# Connectors.net
KiCad netlist of a schematic drawn in Altium Designer
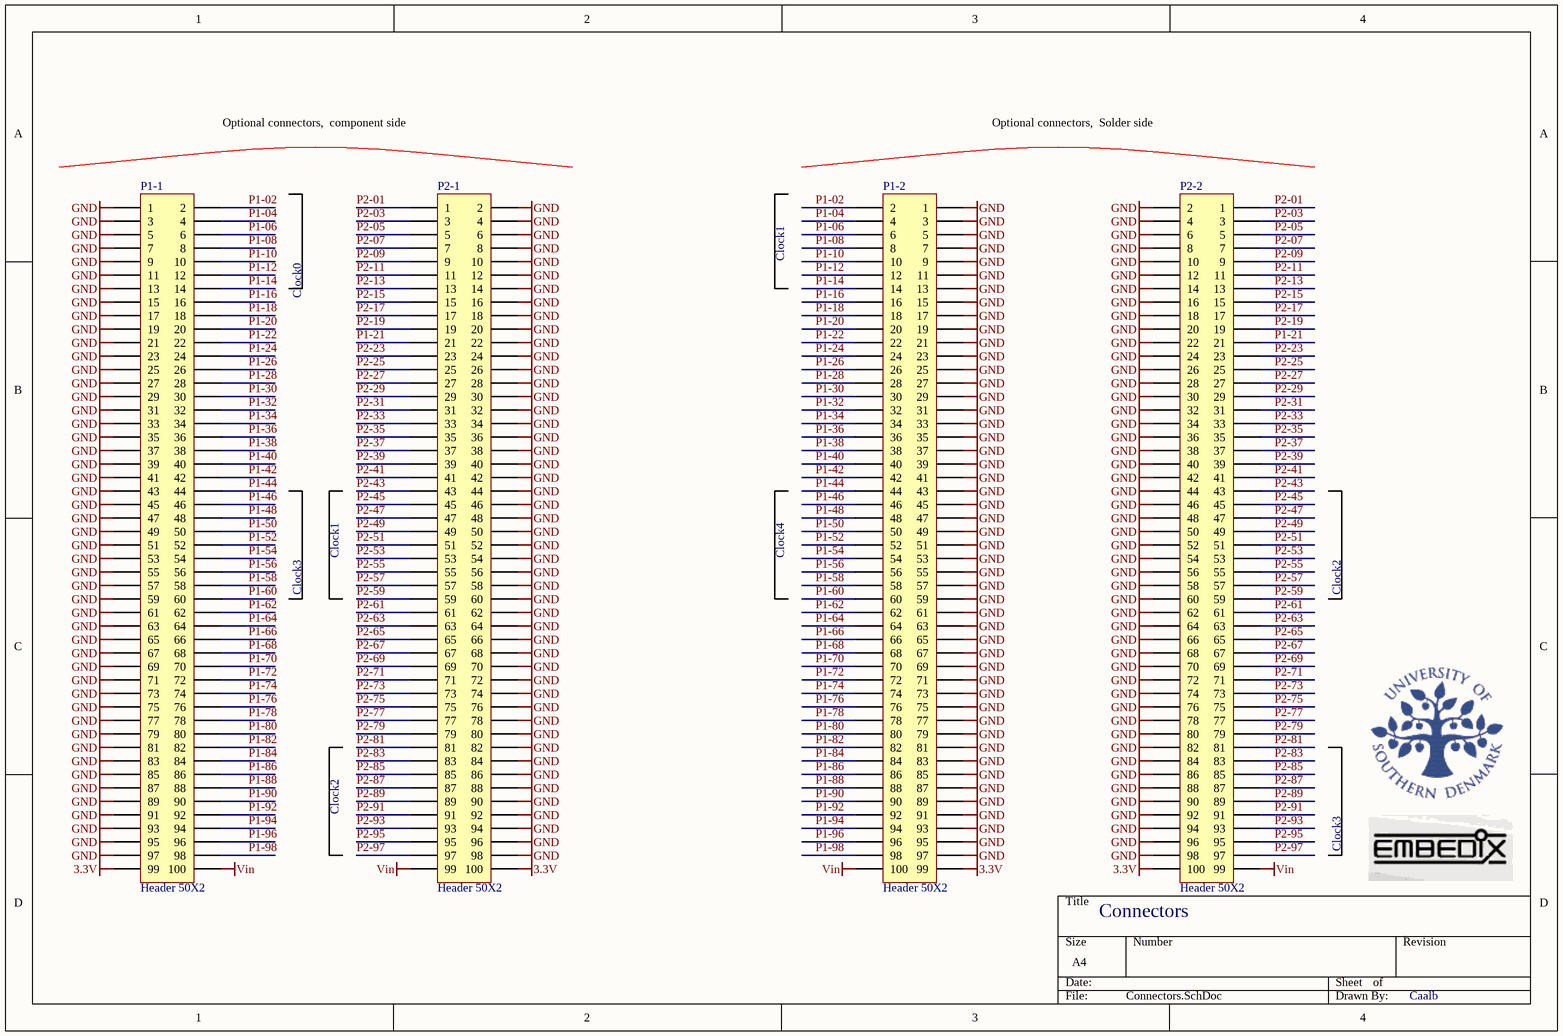
[diagram p0: Connectors.SchDoc]

(export (version "E")
  (design (tool "Eeschema 10.0.6"))
  (components
    (comp (ref "P1-1")
      (value "Header 50X2")
      (footprint "FX8C-100S-SV(91)")
      (description "FX8C-100S-SV(91)")
      (fields (field (name "PUBLISHER") "Altium Limited"))
      (libsource (lib "") (part "Header 50X2_1"))
    )
    (comp (ref "P1-2")
      (value "Header 50X2")
      (footprint "FX8C-100P-SV6(91)")
      (description "FX8C-100P-SV6(91)")
      (fields (field (name "PUBLISHER") "Altium Limited"))
      (libsource (lib "DivLib") (part "Header 50X2"))
    )
    (comp (ref "P2-1")
      (value "Header 50X2")
      (footprint "FX8C-100S-SV(91)")
      (description "FX8C-100S-SV(91)")
      (fields (field (name "PUBLISHER") "Altium Limited"))
      (libsource (lib "") (part "Header 50X2_1"))
    )
    (comp (ref "P2-2")
      (value "Header 50X2")
      (footprint "FX8C-100P-SV6(91)")
      (description "FX8C-100P-SV6(91)")
      (fields (field (name "PUBLISHER") "Altium Limited"))
      (libsource (lib "DivLib") (part "Header 50X2"))
    )
  )
  (nets
    (net (code "1") (name "/P1-02") (class "Default")
      (node (ref "P1-1") (pin "2") (pinfunction "2_2") (pintype "passive"))
      (node (ref "P1-2") (pin "2") (pinfunction "2_2") (pintype "passive"))
    )
    (net (code "2") (name "/P1-04") (class "Default")
      (node (ref "P1-1") (pin "4") (pinfunction "4_4") (pintype "passive"))
      (node (ref "P1-2") (pin "4") (pinfunction "4_4") (pintype "passive"))
    )
    (net (code "3") (name "/P1-06") (class "Default")
      (node (ref "P1-1") (pin "6") (pinfunction "6_6") (pintype "passive"))
      (node (ref "P1-2") (pin "6") (pinfunction "6_6") (pintype "passive"))
    )
    (net (code "4") (name "/P1-08") (class "Default")
      (node (ref "P1-1") (pin "8") (pinfunction "8_8") (pintype "passive"))
      (node (ref "P1-2") (pin "8") (pinfunction "8_8") (pintype "passive"))
    )
    (net (code "5") (name "/P1-10") (class "Default")
      (node (ref "P1-1") (pin "10") (pinfunction "10_10") (pintype "passive"))
      (node (ref "P1-2") (pin "10") (pinfunction "10_10") (pintype "passive"))
    )
    (net (code "6") (name "/P1-12") (class "Default")
      (node (ref "P1-1") (pin "12") (pinfunction "12_12") (pintype "passive"))
      (node (ref "P1-2") (pin "12") (pinfunction "12_12") (pintype "passive"))
    )
    (net (code "7") (name "/P1-14") (class "Default")
      (node (ref "P1-1") (pin "14") (pinfunction "14_14") (pintype "passive"))
      (node (ref "P1-2") (pin "14") (pinfunction "14_14") (pintype "passive"))
    )
    (net (code "8") (name "/P1-16") (class "Default")
      (node (ref "P1-1") (pin "16") (pinfunction "16_16") (pintype "passive"))
      (node (ref "P1-2") (pin "16") (pinfunction "16_16") (pintype "passive"))
    )
    (net (code "9") (name "/P1-18") (class "Default")
      (node (ref "P1-1") (pin "18") (pinfunction "18_18") (pintype "passive"))
      (node (ref "P1-2") (pin "18") (pinfunction "18_18") (pintype "passive"))
    )
    (net (code "10") (name "/P1-20") (class "Default")
      (node (ref "P1-1") (pin "20") (pinfunction "20_20") (pintype "passive"))
      (node (ref "P1-2") (pin "20") (pinfunction "20_20") (pintype "passive"))
    )
    (net (code "11") (name "/P1-21") (class "Default")
      (node (ref "P2-1") (pin "21") (pinfunction "21_21") (pintype "passive"))
      (node (ref "P2-2") (pin "21") (pinfunction "21_21") (pintype "passive"))
    )
    (net (code "12") (name "/P1-22") (class "Default")
      (node (ref "P1-1") (pin "22") (pinfunction "22_22") (pintype "passive"))
      (node (ref "P1-2") (pin "22") (pinfunction "22_22") (pintype "passive"))
    )
    (net (code "13") (name "/P1-24") (class "Default")
      (node (ref "P1-1") (pin "24") (pinfunction "24_24") (pintype "passive"))
      (node (ref "P1-2") (pin "24") (pinfunction "24_24") (pintype "passive"))
    )
    (net (code "14") (name "/P1-26") (class "Default")
      (node (ref "P1-1") (pin "26") (pinfunction "26_26") (pintype "passive"))
      (node (ref "P1-2") (pin "26") (pinfunction "26_26") (pintype "passive"))
    )
    (net (code "15") (name "/P1-28") (class "Default")
      (node (ref "P1-1") (pin "28") (pinfunction "28_28") (pintype "passive"))
      (node (ref "P1-2") (pin "28") (pinfunction "28_28") (pintype "passive"))
    )
    (net (code "16") (name "/P1-30") (class "Default")
      (node (ref "P1-1") (pin "30") (pinfunction "30_30") (pintype "passive"))
      (node (ref "P1-2") (pin "30") (pinfunction "30_30") (pintype "passive"))
    )
    (net (code "17") (name "/P1-32") (class "Default")
      (node (ref "P1-1") (pin "32") (pinfunction "32_32") (pintype "passive"))
      (node (ref "P1-2") (pin "32") (pinfunction "32_32") (pintype "passive"))
    )
    (net (code "18") (name "/P1-34") (class "Default")
      (node (ref "P1-1") (pin "34") (pinfunction "34_34") (pintype "passive"))
      (node (ref "P1-2") (pin "34") (pinfunction "34_34") (pintype "passive"))
    )
    (net (code "19") (name "/P1-36") (class "Default")
      (node (ref "P1-1") (pin "36") (pinfunction "36_36") (pintype "passive"))
      (node (ref "P1-2") (pin "36") (pinfunction "36_36") (pintype "passive"))
    )
    (net (code "20") (name "/P1-38") (class "Default")
      (node (ref "P1-1") (pin "38") (pinfunction "38_38") (pintype "passive"))
      (node (ref "P1-2") (pin "38") (pinfunction "38_38") (pintype "passive"))
    )
    (net (code "21") (name "/P1-40") (class "Default")
      (node (ref "P1-1") (pin "40") (pinfunction "40_40") (pintype "passive"))
      (node (ref "P1-2") (pin "40") (pinfunction "40_40") (pintype "passive"))
    )
    (net (code "22") (name "/P1-42") (class "Default")
      (node (ref "P1-1") (pin "42") (pinfunction "42_42") (pintype "passive"))
      (node (ref "P1-2") (pin "42") (pinfunction "42_42") (pintype "passive"))
    )
    (net (code "23") (name "/P1-44") (class "Default")
      (node (ref "P1-1") (pin "44") (pinfunction "44_44") (pintype "passive"))
      (node (ref "P1-2") (pin "44") (pinfunction "44_44") (pintype "passive"))
    )
    (net (code "24") (name "/P1-46") (class "Default")
      (node (ref "P1-1") (pin "46") (pinfunction "46_46") (pintype "passive"))
      (node (ref "P1-2") (pin "46") (pinfunction "46_46") (pintype "passive"))
    )
    (net (code "25") (name "/P1-48") (class "Default")
      (node (ref "P1-1") (pin "48") (pinfunction "48_48") (pintype "passive"))
      (node (ref "P1-2") (pin "48") (pinfunction "48_48") (pintype "passive"))
    )
    (net (code "26") (name "/P1-50") (class "Default")
      (node (ref "P1-1") (pin "50") (pinfunction "50_50") (pintype "passive"))
      (node (ref "P1-2") (pin "50") (pinfunction "50_50") (pintype "passive"))
    )
    (net (code "27") (name "/P1-52") (class "Default")
      (node (ref "P1-1") (pin "52") (pinfunction "52_52") (pintype "passive"))
      (node (ref "P1-2") (pin "52") (pinfunction "52_52") (pintype "passive"))
    )
    (net (code "28") (name "/P1-54") (class "Default")
      (node (ref "P1-1") (pin "54") (pinfunction "54_54") (pintype "passive"))
      (node (ref "P1-2") (pin "54") (pinfunction "54_54") (pintype "passive"))
    )
    (net (code "29") (name "/P1-56") (class "Default")
      (node (ref "P1-1") (pin "56") (pinfunction "56_56") (pintype "passive"))
      (node (ref "P1-2") (pin "56") (pinfunction "56_56") (pintype "passive"))
    )
    (net (code "30") (name "/P1-58") (class "Default")
      (node (ref "P1-1") (pin "58") (pinfunction "58_58") (pintype "passive"))
      (node (ref "P1-2") (pin "58") (pinfunction "58_58") (pintype "passive"))
    )
    (net (code "31") (name "/P1-60") (class "Default")
      (node (ref "P1-1") (pin "60") (pinfunction "60_60") (pintype "passive"))
      (node (ref "P1-2") (pin "60") (pinfunction "60_60") (pintype "passive"))
    )
    (net (code "32") (name "/P1-62") (class "Default")
      (node (ref "P1-1") (pin "62") (pinfunction "62_62") (pintype "passive"))
      (node (ref "P1-2") (pin "62") (pinfunction "62_62") (pintype "passive"))
    )
    (net (code "33") (name "/P1-64") (class "Default")
      (node (ref "P1-1") (pin "64") (pinfunction "64_64") (pintype "passive"))
      (node (ref "P1-2") (pin "64") (pinfunction "64_64") (pintype "passive"))
    )
    (net (code "34") (name "/P1-66") (class "Default")
      (node (ref "P1-1") (pin "66") (pinfunction "66_66") (pintype "passive"))
      (node (ref "P1-2") (pin "66") (pinfunction "66_66") (pintype "passive"))
    )
    (net (code "35") (name "/P1-68") (class "Default")
      (node (ref "P1-1") (pin "68") (pinfunction "68_68") (pintype "passive"))
      (node (ref "P1-2") (pin "68") (pinfunction "68_68") (pintype "passive"))
    )
    (net (code "36") (name "/P1-70") (class "Default")
      (node (ref "P1-1") (pin "70") (pinfunction "70_70") (pintype "passive"))
      (node (ref "P1-2") (pin "70") (pinfunction "70_70") (pintype "passive"))
    )
    (net (code "37") (name "/P1-72") (class "Default")
      (node (ref "P1-1") (pin "72") (pinfunction "72_72") (pintype "passive"))
      (node (ref "P1-2") (pin "72") (pinfunction "72_72") (pintype "passive"))
    )
    (net (code "38") (name "/P1-74") (class "Default")
      (node (ref "P1-1") (pin "74") (pinfunction "74_74") (pintype "passive"))
      (node (ref "P1-2") (pin "74") (pinfunction "74_74") (pintype "passive"))
    )
    (net (code "39") (name "/P1-76") (class "Default")
      (node (ref "P1-1") (pin "76") (pinfunction "76_76") (pintype "passive"))
      (node (ref "P1-2") (pin "76") (pinfunction "76_76") (pintype "passive"))
    )
    (net (code "40") (name "/P1-78") (class "Default")
      (node (ref "P1-1") (pin "78") (pinfunction "78_78") (pintype "passive"))
      (node (ref "P1-2") (pin "78") (pinfunction "78_78") (pintype "passive"))
    )
    (net (code "41") (name "/P1-80") (class "Default")
      (node (ref "P1-1") (pin "80") (pinfunction "80_80") (pintype "passive"))
      (node (ref "P1-2") (pin "80") (pinfunction "80_80") (pintype "passive"))
    )
    (net (code "42") (name "/P1-82") (class "Default")
      (node (ref "P1-1") (pin "82") (pinfunction "82_82") (pintype "passive"))
      (node (ref "P1-2") (pin "82") (pinfunction "82_82") (pintype "passive"))
    )
    (net (code "43") (name "/P1-84") (class "Default")
      (node (ref "P1-1") (pin "84") (pinfunction "84_84") (pintype "passive"))
      (node (ref "P1-2") (pin "84") (pinfunction "84_84") (pintype "passive"))
    )
    (net (code "44") (name "/P1-86") (class "Default")
      (node (ref "P1-1") (pin "86") (pinfunction "86_86") (pintype "passive"))
      (node (ref "P1-2") (pin "86") (pinfunction "86_86") (pintype "passive"))
    )
    (net (code "45") (name "/P1-88") (class "Default")
      (node (ref "P1-1") (pin "88") (pinfunction "88_88") (pintype "passive"))
      (node (ref "P1-2") (pin "88") (pinfunction "88_88") (pintype "passive"))
    )
    (net (code "46") (name "/P1-90") (class "Default")
      (node (ref "P1-1") (pin "90") (pinfunction "90_90") (pintype "passive"))
      (node (ref "P1-2") (pin "90") (pinfunction "90_90") (pintype "passive"))
    )
    (net (code "47") (name "/P1-92") (class "Default")
      (node (ref "P1-1") (pin "92") (pinfunction "92_92") (pintype "passive"))
      (node (ref "P1-2") (pin "92") (pinfunction "92_92") (pintype "passive"))
    )
    (net (code "48") (name "/P1-94") (class "Default")
      (node (ref "P1-1") (pin "94") (pinfunction "94_94") (pintype "passive"))
      (node (ref "P1-2") (pin "94") (pinfunction "94_94") (pintype "passive"))
    )
    (net (code "49") (name "/P1-96") (class "Default")
      (node (ref "P1-1") (pin "96") (pinfunction "96_96") (pintype "passive"))
      (node (ref "P1-2") (pin "96") (pinfunction "96_96") (pintype "passive"))
    )
    (net (code "50") (name "/P1-98") (class "Default")
      (node (ref "P1-1") (pin "98") (pinfunction "98_98") (pintype "passive"))
      (node (ref "P1-2") (pin "98") (pinfunction "98_98") (pintype "passive"))
    )
    (net (code "51") (name "/P2-01") (class "Default")
      (node (ref "P2-1") (pin "1") (pinfunction "1_1") (pintype "passive"))
      (node (ref "P2-2") (pin "1") (pinfunction "1_1") (pintype "passive"))
    )
    (net (code "52") (name "/P2-03") (class "Default")
      (node (ref "P2-1") (pin "3") (pinfunction "3_3") (pintype "passive"))
      (node (ref "P2-2") (pin "3") (pinfunction "3_3") (pintype "passive"))
    )
    (net (code "53") (name "/P2-05") (class "Default")
      (node (ref "P2-1") (pin "5") (pinfunction "5_5") (pintype "passive"))
      (node (ref "P2-2") (pin "5") (pinfunction "5_5") (pintype "passive"))
    )
    (net (code "54") (name "/P2-07") (class "Default")
      (node (ref "P2-1") (pin "7") (pinfunction "7_7") (pintype "passive"))
      (node (ref "P2-2") (pin "7") (pinfunction "7_7") (pintype "passive"))
    )
    (net (code "55") (name "/P2-09") (class "Default")
      (node (ref "P2-1") (pin "9") (pinfunction "9_9") (pintype "passive"))
      (node (ref "P2-2") (pin "9") (pinfunction "9_9") (pintype "passive"))
    )
    (net (code "56") (name "/P2-11") (class "Default")
      (node (ref "P2-1") (pin "11") (pinfunction "11_11") (pintype "passive"))
      (node (ref "P2-2") (pin "11") (pinfunction "11_11") (pintype "passive"))
    )
    (net (code "57") (name "/P2-13") (class "Default")
      (node (ref "P2-1") (pin "13") (pinfunction "13_13") (pintype "passive"))
      (node (ref "P2-2") (pin "13") (pinfunction "13_13") (pintype "passive"))
    )
    (net (code "58") (name "/P2-15") (class "Default")
      (node (ref "P2-1") (pin "15") (pinfunction "15_15") (pintype "passive"))
      (node (ref "P2-2") (pin "15") (pinfunction "15_15") (pintype "passive"))
    )
    (net (code "59") (name "/P2-17") (class "Default")
      (node (ref "P2-1") (pin "17") (pinfunction "17_17") (pintype "passive"))
      (node (ref "P2-2") (pin "17") (pinfunction "17_17") (pintype "passive"))
    )
    (net (code "60") (name "/P2-19") (class "Default")
      (node (ref "P2-1") (pin "19") (pinfunction "19_19") (pintype "passive"))
      (node (ref "P2-2") (pin "19") (pinfunction "19_19") (pintype "passive"))
    )
    (net (code "61") (name "/P2-23") (class "Default")
      (node (ref "P2-1") (pin "23") (pinfunction "23_23") (pintype "passive"))
      (node (ref "P2-2") (pin "23") (pinfunction "23_23") (pintype "passive"))
    )
    (net (code "62") (name "/P2-25") (class "Default")
      (node (ref "P2-1") (pin "25") (pinfunction "25_25") (pintype "passive"))
      (node (ref "P2-2") (pin "25") (pinfunction "25_25") (pintype "passive"))
    )
    (net (code "63") (name "/P2-27") (class "Default")
      (node (ref "P2-1") (pin "27") (pinfunction "27_27") (pintype "passive"))
      (node (ref "P2-2") (pin "27") (pinfunction "27_27") (pintype "passive"))
    )
    (net (code "64") (name "/P2-29") (class "Default")
      (node (ref "P2-1") (pin "29") (pinfunction "29_29") (pintype "passive"))
      (node (ref "P2-2") (pin "29") (pinfunction "29_29") (pintype "passive"))
    )
    (net (code "65") (name "/P2-31") (class "Default")
      (node (ref "P2-1") (pin "31") (pinfunction "31_31") (pintype "passive"))
      (node (ref "P2-2") (pin "31") (pinfunction "31_31") (pintype "passive"))
    )
    (net (code "66") (name "/P2-33") (class "Default")
      (node (ref "P2-1") (pin "33") (pinfunction "33_33") (pintype "passive"))
      (node (ref "P2-2") (pin "33") (pinfunction "33_33") (pintype "passive"))
    )
    (net (code "67") (name "/P2-35") (class "Default")
      (node (ref "P2-1") (pin "35") (pinfunction "35_35") (pintype "passive"))
      (node (ref "P2-2") (pin "35") (pinfunction "35_35") (pintype "passive"))
    )
    (net (code "68") (name "/P2-37") (class "Default")
      (node (ref "P2-1") (pin "37") (pinfunction "37_37") (pintype "passive"))
      (node (ref "P2-2") (pin "37") (pinfunction "37_37") (pintype "passive"))
    )
    (net (code "69") (name "/P2-39") (class "Default")
      (node (ref "P2-1") (pin "39") (pinfunction "39_39") (pintype "passive"))
      (node (ref "P2-2") (pin "39") (pinfunction "39_39") (pintype "passive"))
    )
    (net (code "70") (name "/P2-41") (class "Default")
      (node (ref "P2-1") (pin "41") (pinfunction "41_41") (pintype "passive"))
      (node (ref "P2-2") (pin "41") (pinfunction "41_41") (pintype "passive"))
    )
    (net (code "71") (name "/P2-43") (class "Default")
      (node (ref "P2-1") (pin "43") (pinfunction "43_43") (pintype "passive"))
      (node (ref "P2-2") (pin "43") (pinfunction "43_43") (pintype "passive"))
    )
    (net (code "72") (name "/P2-45") (class "Default")
      (node (ref "P2-1") (pin "45") (pinfunction "45_45") (pintype "passive"))
      (node (ref "P2-2") (pin "45") (pinfunction "45_45") (pintype "passive"))
    )
    (net (code "73") (name "/P2-47") (class "Default")
      (node (ref "P2-1") (pin "47") (pinfunction "47_47") (pintype "passive"))
      (node (ref "P2-2") (pin "47") (pinfunction "47_47") (pintype "passive"))
    )
    (net (code "74") (name "/P2-49") (class "Default")
      (node (ref "P2-1") (pin "49") (pinfunction "49_49") (pintype "passive"))
      (node (ref "P2-2") (pin "49") (pinfunction "49_49") (pintype "passive"))
    )
    (net (code "75") (name "/P2-51") (class "Default")
      (node (ref "P2-1") (pin "51") (pinfunction "51_51") (pintype "passive"))
      (node (ref "P2-2") (pin "51") (pinfunction "51_51") (pintype "passive"))
    )
    (net (code "76") (name "/P2-53") (class "Default")
      (node (ref "P2-1") (pin "53") (pinfunction "53_53") (pintype "passive"))
      (node (ref "P2-2") (pin "53") (pinfunction "53_53") (pintype "passive"))
    )
    (net (code "77") (name "/P2-55") (class "Default")
      (node (ref "P2-1") (pin "55") (pinfunction "55_55") (pintype "passive"))
      (node (ref "P2-2") (pin "55") (pinfunction "55_55") (pintype "passive"))
    )
    (net (code "78") (name "/P2-57") (class "Default")
      (node (ref "P2-1") (pin "57") (pinfunction "57_57") (pintype "passive"))
      (node (ref "P2-2") (pin "57") (pinfunction "57_57") (pintype "passive"))
    )
    (net (code "79") (name "/P2-59") (class "Default")
      (node (ref "P2-1") (pin "59") (pinfunction "59_59") (pintype "passive"))
      (node (ref "P2-2") (pin "59") (pinfunction "59_59") (pintype "passive"))
    )
    (net (code "80") (name "/P2-61") (class "Default")
      (node (ref "P2-1") (pin "61") (pinfunction "61_61") (pintype "passive"))
      (node (ref "P2-2") (pin "61") (pinfunction "61_61") (pintype "passive"))
    )
    (net (code "81") (name "/P2-63") (class "Default")
      (node (ref "P2-1") (pin "63") (pinfunction "63_63") (pintype "passive"))
      (node (ref "P2-2") (pin "63") (pinfunction "63_63") (pintype "passive"))
    )
    (net (code "82") (name "/P2-65") (class "Default")
      (node (ref "P2-1") (pin "65") (pinfunction "65_65") (pintype "passive"))
      (node (ref "P2-2") (pin "65") (pinfunction "65_65") (pintype "passive"))
    )
    (net (code "83") (name "/P2-67") (class "Default")
      (node (ref "P2-1") (pin "67") (pinfunction "67_67") (pintype "passive"))
      (node (ref "P2-2") (pin "67") (pinfunction "67_67") (pintype "passive"))
    )
    (net (code "84") (name "/P2-69") (class "Default")
      (node (ref "P2-1") (pin "69") (pinfunction "69_69") (pintype "passive"))
      (node (ref "P2-2") (pin "69") (pinfunction "69_69") (pintype "passive"))
    )
    (net (code "85") (name "/P2-71") (class "Default")
      (node (ref "P2-1") (pin "71") (pinfunction "71_71") (pintype "passive"))
      (node (ref "P2-2") (pin "71") (pinfunction "71_71") (pintype "passive"))
    )
    (net (code "86") (name "/P2-73") (class "Default")
      (node (ref "P2-1") (pin "73") (pinfunction "73_73") (pintype "passive"))
      (node (ref "P2-2") (pin "73") (pinfunction "73_73") (pintype "passive"))
    )
    (net (code "87") (name "/P2-75") (class "Default")
      (node (ref "P2-1") (pin "75") (pinfunction "75_75") (pintype "passive"))
      (node (ref "P2-2") (pin "75") (pinfunction "75_75") (pintype "passive"))
    )
    (net (code "88") (name "/P2-77") (class "Default")
      (node (ref "P2-1") (pin "77") (pinfunction "77_77") (pintype "passive"))
      (node (ref "P2-2") (pin "77") (pinfunction "77_77") (pintype "passive"))
    )
    (net (code "89") (name "/P2-79") (class "Default")
      (node (ref "P2-1") (pin "79") (pinfunction "79_79") (pintype "passive"))
      (node (ref "P2-2") (pin "79") (pinfunction "79_79") (pintype "passive"))
    )
    (net (code "90") (name "/P2-81") (class "Default")
      (node (ref "P2-1") (pin "81") (pinfunction "81_81") (pintype "passive"))
      (node (ref "P2-2") (pin "81") (pinfunction "81_81") (pintype "passive"))
    )
    (net (code "91") (name "/P2-83") (class "Default")
      (node (ref "P2-1") (pin "83") (pinfunction "83_83") (pintype "passive"))
      (node (ref "P2-2") (pin "83") (pinfunction "83_83") (pintype "passive"))
    )
    (net (code "92") (name "/P2-85") (class "Default")
      (node (ref "P2-1") (pin "85") (pinfunction "85_85") (pintype "passive"))
      (node (ref "P2-2") (pin "85") (pinfunction "85_85") (pintype "passive"))
    )
    (net (code "93") (name "/P2-87") (class "Default")
      (node (ref "P2-1") (pin "87") (pinfunction "87_87") (pintype "passive"))
      (node (ref "P2-2") (pin "87") (pinfunction "87_87") (pintype "passive"))
    )
    (net (code "94") (name "/P2-89") (class "Default")
      (node (ref "P2-1") (pin "89") (pinfunction "89_89") (pintype "passive"))
      (node (ref "P2-2") (pin "89") (pinfunction "89_89") (pintype "passive"))
    )
    (net (code "95") (name "/P2-91") (class "Default")
      (node (ref "P2-1") (pin "91") (pinfunction "91_91") (pintype "passive"))
      (node (ref "P2-2") (pin "91") (pinfunction "91_91") (pintype "passive"))
    )
    (net (code "96") (name "/P2-93") (class "Default")
      (node (ref "P2-1") (pin "93") (pinfunction "93_93") (pintype "passive"))
      (node (ref "P2-2") (pin "93") (pinfunction "93_93") (pintype "passive"))
    )
    (net (code "97") (name "/P2-95") (class "Default")
      (node (ref "P2-1") (pin "95") (pinfunction "95_95") (pintype "passive"))
      (node (ref "P2-2") (pin "95") (pinfunction "95_95") (pintype "passive"))
    )
    (net (code "98") (name "/P2-97") (class "Default")
      (node (ref "P2-1") (pin "97") (pinfunction "97_97") (pintype "passive"))
      (node (ref "P2-2") (pin "97") (pinfunction "97_97") (pintype "passive"))
    )
    (net (code "99") (name "3.3V") (class "Default")
      (node (ref "P1-1") (pin "99") (pinfunction "99_99") (pintype "passive"))
      (node (ref "P1-2") (pin "99") (pinfunction "99_99") (pintype "passive"))
      (node (ref "P2-1") (pin "100") (pinfunction "100_100") (pintype "passive"))
      (node (ref "P2-2") (pin "100") (pinfunction "100_100") (pintype "passive"))
    )
    (net (code "100") (name "GND") (class "Default")
      (node (ref "P1-1") (pin "1") (pinfunction "1_1") (pintype "passive"))
      (node (ref "P1-1") (pin "11") (pinfunction "11_11") (pintype "passive"))
      (node (ref "P1-1") (pin "13") (pinfunction "13_13") (pintype "passive"))
      (node (ref "P1-1") (pin "15") (pinfunction "15_15") (pintype "passive"))
      (node (ref "P1-1") (pin "17") (pinfunction "17_17") (pintype "passive"))
      (node (ref "P1-1") (pin "19") (pinfunction "19_19") (pintype "passive"))
      (node (ref "P1-1") (pin "21") (pinfunction "21_21") (pintype "passive"))
      (node (ref "P1-1") (pin "23") (pinfunction "23_23") (pintype "passive"))
      (node (ref "P1-1") (pin "25") (pinfunction "25_25") (pintype "passive"))
      (node (ref "P1-1") (pin "27") (pinfunction "27_27") (pintype "passive"))
      (node (ref "P1-1") (pin "29") (pinfunction "29_29") (pintype "passive"))
      (node (ref "P1-1") (pin "3") (pinfunction "3_3") (pintype "passive"))
      (node (ref "P1-1") (pin "31") (pinfunction "31_31") (pintype "passive"))
      (node (ref "P1-1") (pin "33") (pinfunction "33_33") (pintype "passive"))
      (node (ref "P1-1") (pin "35") (pinfunction "35_35") (pintype "passive"))
      (node (ref "P1-1") (pin "37") (pinfunction "37_37") (pintype "passive"))
      (node (ref "P1-1") (pin "39") (pinfunction "39_39") (pintype "passive"))
      (node (ref "P1-1") (pin "41") (pinfunction "41_41") (pintype "passive"))
      (node (ref "P1-1") (pin "43") (pinfunction "43_43") (pintype "passive"))
      (node (ref "P1-1") (pin "45") (pinfunction "45_45") (pintype "passive"))
      (node (ref "P1-1") (pin "47") (pinfunction "47_47") (pintype "passive"))
      (node (ref "P1-1") (pin "49") (pinfunction "49_49") (pintype "passive"))
      (node (ref "P1-1") (pin "5") (pinfunction "5_5") (pintype "passive"))
      (node (ref "P1-1") (pin "51") (pinfunction "51_51") (pintype "passive"))
      (node (ref "P1-1") (pin "53") (pinfunction "53_53") (pintype "passive"))
      (node (ref "P1-1") (pin "55") (pinfunction "55_55") (pintype "passive"))
      (node (ref "P1-1") (pin "57") (pinfunction "57_57") (pintype "passive"))
      (node (ref "P1-1") (pin "59") (pinfunction "59_59") (pintype "passive"))
      (node (ref "P1-1") (pin "61") (pinfunction "61_61") (pintype "passive"))
      (node (ref "P1-1") (pin "63") (pinfunction "63_63") (pintype "passive"))
      (node (ref "P1-1") (pin "65") (pinfunction "65_65") (pintype "passive"))
      (node (ref "P1-1") (pin "67") (pinfunction "67_67") (pintype "passive"))
      (node (ref "P1-1") (pin "69") (pinfunction "69_69") (pintype "passive"))
      (node (ref "P1-1") (pin "7") (pinfunction "7_7") (pintype "passive"))
      (node (ref "P1-1") (pin "71") (pinfunction "71_71") (pintype "passive"))
      (node (ref "P1-1") (pin "73") (pinfunction "73_73") (pintype "passive"))
      (node (ref "P1-1") (pin "75") (pinfunction "75_75") (pintype "passive"))
      (node (ref "P1-1") (pin "77") (pinfunction "77_77") (pintype "passive"))
      (node (ref "P1-1") (pin "79") (pinfunction "79_79") (pintype "passive"))
      (node (ref "P1-1") (pin "81") (pinfunction "81_81") (pintype "passive"))
      (node (ref "P1-1") (pin "83") (pinfunction "83_83") (pintype "passive"))
      (node (ref "P1-1") (pin "85") (pinfunction "85_85") (pintype "passive"))
      (node (ref "P1-1") (pin "87") (pinfunction "87_87") (pintype "passive"))
      (node (ref "P1-1") (pin "89") (pinfunction "89_89") (pintype "passive"))
      (node (ref "P1-1") (pin "9") (pinfunction "9_9") (pintype "passive"))
      (node (ref "P1-1") (pin "91") (pinfunction "91_91") (pintype "passive"))
      (node (ref "P1-1") (pin "93") (pinfunction "93_93") (pintype "passive"))
      (node (ref "P1-1") (pin "95") (pinfunction "95_95") (pintype "passive"))
      (node (ref "P1-1") (pin "97") (pinfunction "97_97") (pintype "passive"))
      (node (ref "P1-2") (pin "1") (pinfunction "1_1") (pintype "passive"))
      (node (ref "P1-2") (pin "11") (pinfunction "11_11") (pintype "passive"))
      (node (ref "P1-2") (pin "13") (pinfunction "13_13") (pintype "passive"))
      (node (ref "P1-2") (pin "15") (pinfunction "15_15") (pintype "passive"))
      (node (ref "P1-2") (pin "17") (pinfunction "17_17") (pintype "passive"))
      (node (ref "P1-2") (pin "19") (pinfunction "19_19") (pintype "passive"))
      (node (ref "P1-2") (pin "21") (pinfunction "21_21") (pintype "passive"))
      (node (ref "P1-2") (pin "23") (pinfunction "23_23") (pintype "passive"))
      (node (ref "P1-2") (pin "25") (pinfunction "25_25") (pintype "passive"))
      (node (ref "P1-2") (pin "27") (pinfunction "27_27") (pintype "passive"))
      (node (ref "P1-2") (pin "29") (pinfunction "29_29") (pintype "passive"))
      (node (ref "P1-2") (pin "3") (pinfunction "3_3") (pintype "passive"))
      (node (ref "P1-2") (pin "31") (pinfunction "31_31") (pintype "passive"))
      (node (ref "P1-2") (pin "33") (pinfunction "33_33") (pintype "passive"))
      (node (ref "P1-2") (pin "35") (pinfunction "35_35") (pintype "passive"))
      (node (ref "P1-2") (pin "37") (pinfunction "37_37") (pintype "passive"))
      (node (ref "P1-2") (pin "39") (pinfunction "39_39") (pintype "passive"))
      (node (ref "P1-2") (pin "41") (pinfunction "41_41") (pintype "passive"))
      (node (ref "P1-2") (pin "43") (pinfunction "43_43") (pintype "passive"))
      (node (ref "P1-2") (pin "45") (pinfunction "45_45") (pintype "passive"))
      (node (ref "P1-2") (pin "47") (pinfunction "47_47") (pintype "passive"))
      (node (ref "P1-2") (pin "49") (pinfunction "49_49") (pintype "passive"))
      (node (ref "P1-2") (pin "5") (pinfunction "5_5") (pintype "passive"))
      (node (ref "P1-2") (pin "51") (pinfunction "51_51") (pintype "passive"))
      (node (ref "P1-2") (pin "53") (pinfunction "53_53") (pintype "passive"))
      (node (ref "P1-2") (pin "55") (pinfunction "55_55") (pintype "passive"))
      (node (ref "P1-2") (pin "57") (pinfunction "57_57") (pintype "passive"))
      (node (ref "P1-2") (pin "59") (pinfunction "59_59") (pintype "passive"))
      (node (ref "P1-2") (pin "61") (pinfunction "61_61") (pintype "passive"))
      (node (ref "P1-2") (pin "63") (pinfunction "63_63") (pintype "passive"))
      (node (ref "P1-2") (pin "65") (pinfunction "65_65") (pintype "passive"))
      (node (ref "P1-2") (pin "67") (pinfunction "67_67") (pintype "passive"))
      (node (ref "P1-2") (pin "69") (pinfunction "69_69") (pintype "passive"))
      (node (ref "P1-2") (pin "7") (pinfunction "7_7") (pintype "passive"))
      (node (ref "P1-2") (pin "71") (pinfunction "71_71") (pintype "passive"))
      (node (ref "P1-2") (pin "73") (pinfunction "73_73") (pintype "passive"))
      (node (ref "P1-2") (pin "75") (pinfunction "75_75") (pintype "passive"))
      (node (ref "P1-2") (pin "77") (pinfunction "77_77") (pintype "passive"))
      (node (ref "P1-2") (pin "79") (pinfunction "79_79") (pintype "passive"))
      (node (ref "P1-2") (pin "81") (pinfunction "81_81") (pintype "passive"))
      (node (ref "P1-2") (pin "83") (pinfunction "83_83") (pintype "passive"))
      (node (ref "P1-2") (pin "85") (pinfunction "85_85") (pintype "passive"))
      (node (ref "P1-2") (pin "87") (pinfunction "87_87") (pintype "passive"))
      (node (ref "P1-2") (pin "89") (pinfunction "89_89") (pintype "passive"))
      (node (ref "P1-2") (pin "9") (pinfunction "9_9") (pintype "passive"))
      (node (ref "P1-2") (pin "91") (pinfunction "91_91") (pintype "passive"))
      (node (ref "P1-2") (pin "93") (pinfunction "93_93") (pintype "passive"))
      (node (ref "P1-2") (pin "95") (pinfunction "95_95") (pintype "passive"))
      (node (ref "P1-2") (pin "97") (pinfunction "97_97") (pintype "passive"))
      (node (ref "P2-1") (pin "10") (pinfunction "10_10") (pintype "passive"))
      (node (ref "P2-1") (pin "12") (pinfunction "12_12") (pintype "passive"))
      (node (ref "P2-1") (pin "14") (pinfunction "14_14") (pintype "passive"))
      (node (ref "P2-1") (pin "16") (pinfunction "16_16") (pintype "passive"))
      (node (ref "P2-1") (pin "18") (pinfunction "18_18") (pintype "passive"))
      (node (ref "P2-1") (pin "2") (pinfunction "2_2") (pintype "passive"))
      (node (ref "P2-1") (pin "20") (pinfunction "20_20") (pintype "passive"))
      (node (ref "P2-1") (pin "22") (pinfunction "22_22") (pintype "passive"))
      (node (ref "P2-1") (pin "24") (pinfunction "24_24") (pintype "passive"))
      (node (ref "P2-1") (pin "26") (pinfunction "26_26") (pintype "passive"))
      (node (ref "P2-1") (pin "28") (pinfunction "28_28") (pintype "passive"))
      (node (ref "P2-1") (pin "30") (pinfunction "30_30") (pintype "passive"))
      (node (ref "P2-1") (pin "32") (pinfunction "32_32") (pintype "passive"))
      (node (ref "P2-1") (pin "34") (pinfunction "34_34") (pintype "passive"))
      (node (ref "P2-1") (pin "36") (pinfunction "36_36") (pintype "passive"))
      (node (ref "P2-1") (pin "38") (pinfunction "38_38") (pintype "passive"))
      (node (ref "P2-1") (pin "4") (pinfunction "4_4") (pintype "passive"))
      (node (ref "P2-1") (pin "40") (pinfunction "40_40") (pintype "passive"))
      (node (ref "P2-1") (pin "42") (pinfunction "42_42") (pintype "passive"))
      (node (ref "P2-1") (pin "44") (pinfunction "44_44") (pintype "passive"))
      (node (ref "P2-1") (pin "46") (pinfunction "46_46") (pintype "passive"))
      (node (ref "P2-1") (pin "48") (pinfunction "48_48") (pintype "passive"))
      (node (ref "P2-1") (pin "50") (pinfunction "50_50") (pintype "passive"))
      (node (ref "P2-1") (pin "52") (pinfunction "52_52") (pintype "passive"))
      (node (ref "P2-1") (pin "54") (pinfunction "54_54") (pintype "passive"))
      (node (ref "P2-1") (pin "56") (pinfunction "56_56") (pintype "passive"))
      (node (ref "P2-1") (pin "58") (pinfunction "58_58") (pintype "passive"))
      (node (ref "P2-1") (pin "6") (pinfunction "6_6") (pintype "passive"))
      (node (ref "P2-1") (pin "60") (pinfunction "60_60") (pintype "passive"))
      (node (ref "P2-1") (pin "62") (pinfunction "62_62") (pintype "passive"))
      (node (ref "P2-1") (pin "64") (pinfunction "64_64") (pintype "passive"))
      (node (ref "P2-1") (pin "66") (pinfunction "66_66") (pintype "passive"))
      (node (ref "P2-1") (pin "68") (pinfunction "68_68") (pintype "passive"))
      (node (ref "P2-1") (pin "70") (pinfunction "70_70") (pintype "passive"))
      (node (ref "P2-1") (pin "72") (pinfunction "72_72") (pintype "passive"))
      (node (ref "P2-1") (pin "74") (pinfunction "74_74") (pintype "passive"))
      (node (ref "P2-1") (pin "76") (pinfunction "76_76") (pintype "passive"))
      (node (ref "P2-1") (pin "78") (pinfunction "78_78") (pintype "passive"))
      (node (ref "P2-1") (pin "8") (pinfunction "8_8") (pintype "passive"))
      (node (ref "P2-1") (pin "80") (pinfunction "80_80") (pintype "passive"))
      (node (ref "P2-1") (pin "82") (pinfunction "82_82") (pintype "passive"))
      (node (ref "P2-1") (pin "84") (pinfunction "84_84") (pintype "passive"))
      (node (ref "P2-1") (pin "86") (pinfunction "86_86") (pintype "passive"))
      (node (ref "P2-1") (pin "88") (pinfunction "88_88") (pintype "passive"))
      (node (ref "P2-1") (pin "90") (pinfunction "90_90") (pintype "passive"))
      (node (ref "P2-1") (pin "92") (pinfunction "92_92") (pintype "passive"))
      (node (ref "P2-1") (pin "94") (pinfunction "94_94") (pintype "passive"))
      (node (ref "P2-1") (pin "96") (pinfunction "96_96") (pintype "passive"))
      (node (ref "P2-1") (pin "98") (pinfunction "98_98") (pintype "passive"))
      (node (ref "P2-2") (pin "10") (pinfunction "10_10") (pintype "passive"))
      (node (ref "P2-2") (pin "12") (pinfunction "12_12") (pintype "passive"))
      (node (ref "P2-2") (pin "14") (pinfunction "14_14") (pintype "passive"))
      (node (ref "P2-2") (pin "16") (pinfunction "16_16") (pintype "passive"))
      (node (ref "P2-2") (pin "18") (pinfunction "18_18") (pintype "passive"))
      (node (ref "P2-2") (pin "2") (pinfunction "2_2") (pintype "passive"))
      (node (ref "P2-2") (pin "20") (pinfunction "20_20") (pintype "passive"))
      (node (ref "P2-2") (pin "22") (pinfunction "22_22") (pintype "passive"))
      (node (ref "P2-2") (pin "24") (pinfunction "24_24") (pintype "passive"))
      (node (ref "P2-2") (pin "26") (pinfunction "26_26") (pintype "passive"))
      (node (ref "P2-2") (pin "28") (pinfunction "28_28") (pintype "passive"))
      (node (ref "P2-2") (pin "30") (pinfunction "30_30") (pintype "passive"))
      (node (ref "P2-2") (pin "32") (pinfunction "32_32") (pintype "passive"))
      (node (ref "P2-2") (pin "34") (pinfunction "34_34") (pintype "passive"))
      (node (ref "P2-2") (pin "36") (pinfunction "36_36") (pintype "passive"))
      (node (ref "P2-2") (pin "38") (pinfunction "38_38") (pintype "passive"))
      (node (ref "P2-2") (pin "4") (pinfunction "4_4") (pintype "passive"))
      (node (ref "P2-2") (pin "40") (pinfunction "40_40") (pintype "passive"))
      (node (ref "P2-2") (pin "42") (pinfunction "42_42") (pintype "passive"))
      (node (ref "P2-2") (pin "44") (pinfunction "44_44") (pintype "passive"))
      (node (ref "P2-2") (pin "46") (pinfunction "46_46") (pintype "passive"))
      (node (ref "P2-2") (pin "48") (pinfunction "48_48") (pintype "passive"))
      (node (ref "P2-2") (pin "50") (pinfunction "50_50") (pintype "passive"))
      (node (ref "P2-2") (pin "52") (pinfunction "52_52") (pintype "passive"))
      (node (ref "P2-2") (pin "54") (pinfunction "54_54") (pintype "passive"))
      (node (ref "P2-2") (pin "56") (pinfunction "56_56") (pintype "passive"))
      (node (ref "P2-2") (pin "58") (pinfunction "58_58") (pintype "passive"))
      (node (ref "P2-2") (pin "6") (pinfunction "6_6") (pintype "passive"))
      (node (ref "P2-2") (pin "60") (pinfunction "60_60") (pintype "passive"))
      (node (ref "P2-2") (pin "62") (pinfunction "62_62") (pintype "passive"))
      (node (ref "P2-2") (pin "64") (pinfunction "64_64") (pintype "passive"))
      (node (ref "P2-2") (pin "66") (pinfunction "66_66") (pintype "passive"))
      (node (ref "P2-2") (pin "68") (pinfunction "68_68") (pintype "passive"))
      (node (ref "P2-2") (pin "70") (pinfunction "70_70") (pintype "passive"))
      (node (ref "P2-2") (pin "72") (pinfunction "72_72") (pintype "passive"))
      (node (ref "P2-2") (pin "74") (pinfunction "74_74") (pintype "passive"))
      (node (ref "P2-2") (pin "76") (pinfunction "76_76") (pintype "passive"))
      (node (ref "P2-2") (pin "78") (pinfunction "78_78") (pintype "passive"))
      (node (ref "P2-2") (pin "8") (pinfunction "8_8") (pintype "passive"))
      (node (ref "P2-2") (pin "80") (pinfunction "80_80") (pintype "passive"))
      (node (ref "P2-2") (pin "82") (pinfunction "82_82") (pintype "passive"))
      (node (ref "P2-2") (pin "84") (pinfunction "84_84") (pintype "passive"))
      (node (ref "P2-2") (pin "86") (pinfunction "86_86") (pintype "passive"))
      (node (ref "P2-2") (pin "88") (pinfunction "88_88") (pintype "passive"))
      (node (ref "P2-2") (pin "90") (pinfunction "90_90") (pintype "passive"))
      (node (ref "P2-2") (pin "92") (pinfunction "92_92") (pintype "passive"))
      (node (ref "P2-2") (pin "94") (pinfunction "94_94") (pintype "passive"))
      (node (ref "P2-2") (pin "96") (pinfunction "96_96") (pintype "passive"))
      (node (ref "P2-2") (pin "98") (pinfunction "98_98") (pintype "passive"))
    )
    (net (code "101") (name "Vin") (class "Default")
      (node (ref "P1-1") (pin "100") (pinfunction "100_100") (pintype "passive"))
      (node (ref "P1-2") (pin "100") (pinfunction "100_100") (pintype "passive"))
      (node (ref "P2-1") (pin "99") (pinfunction "99_99") (pintype "passive"))
      (node (ref "P2-2") (pin "99") (pinfunction "99_99") (pintype "passive"))
    )
  )
)
